# project2.net
KiCad netlist of a schematic drawn in EAGLE
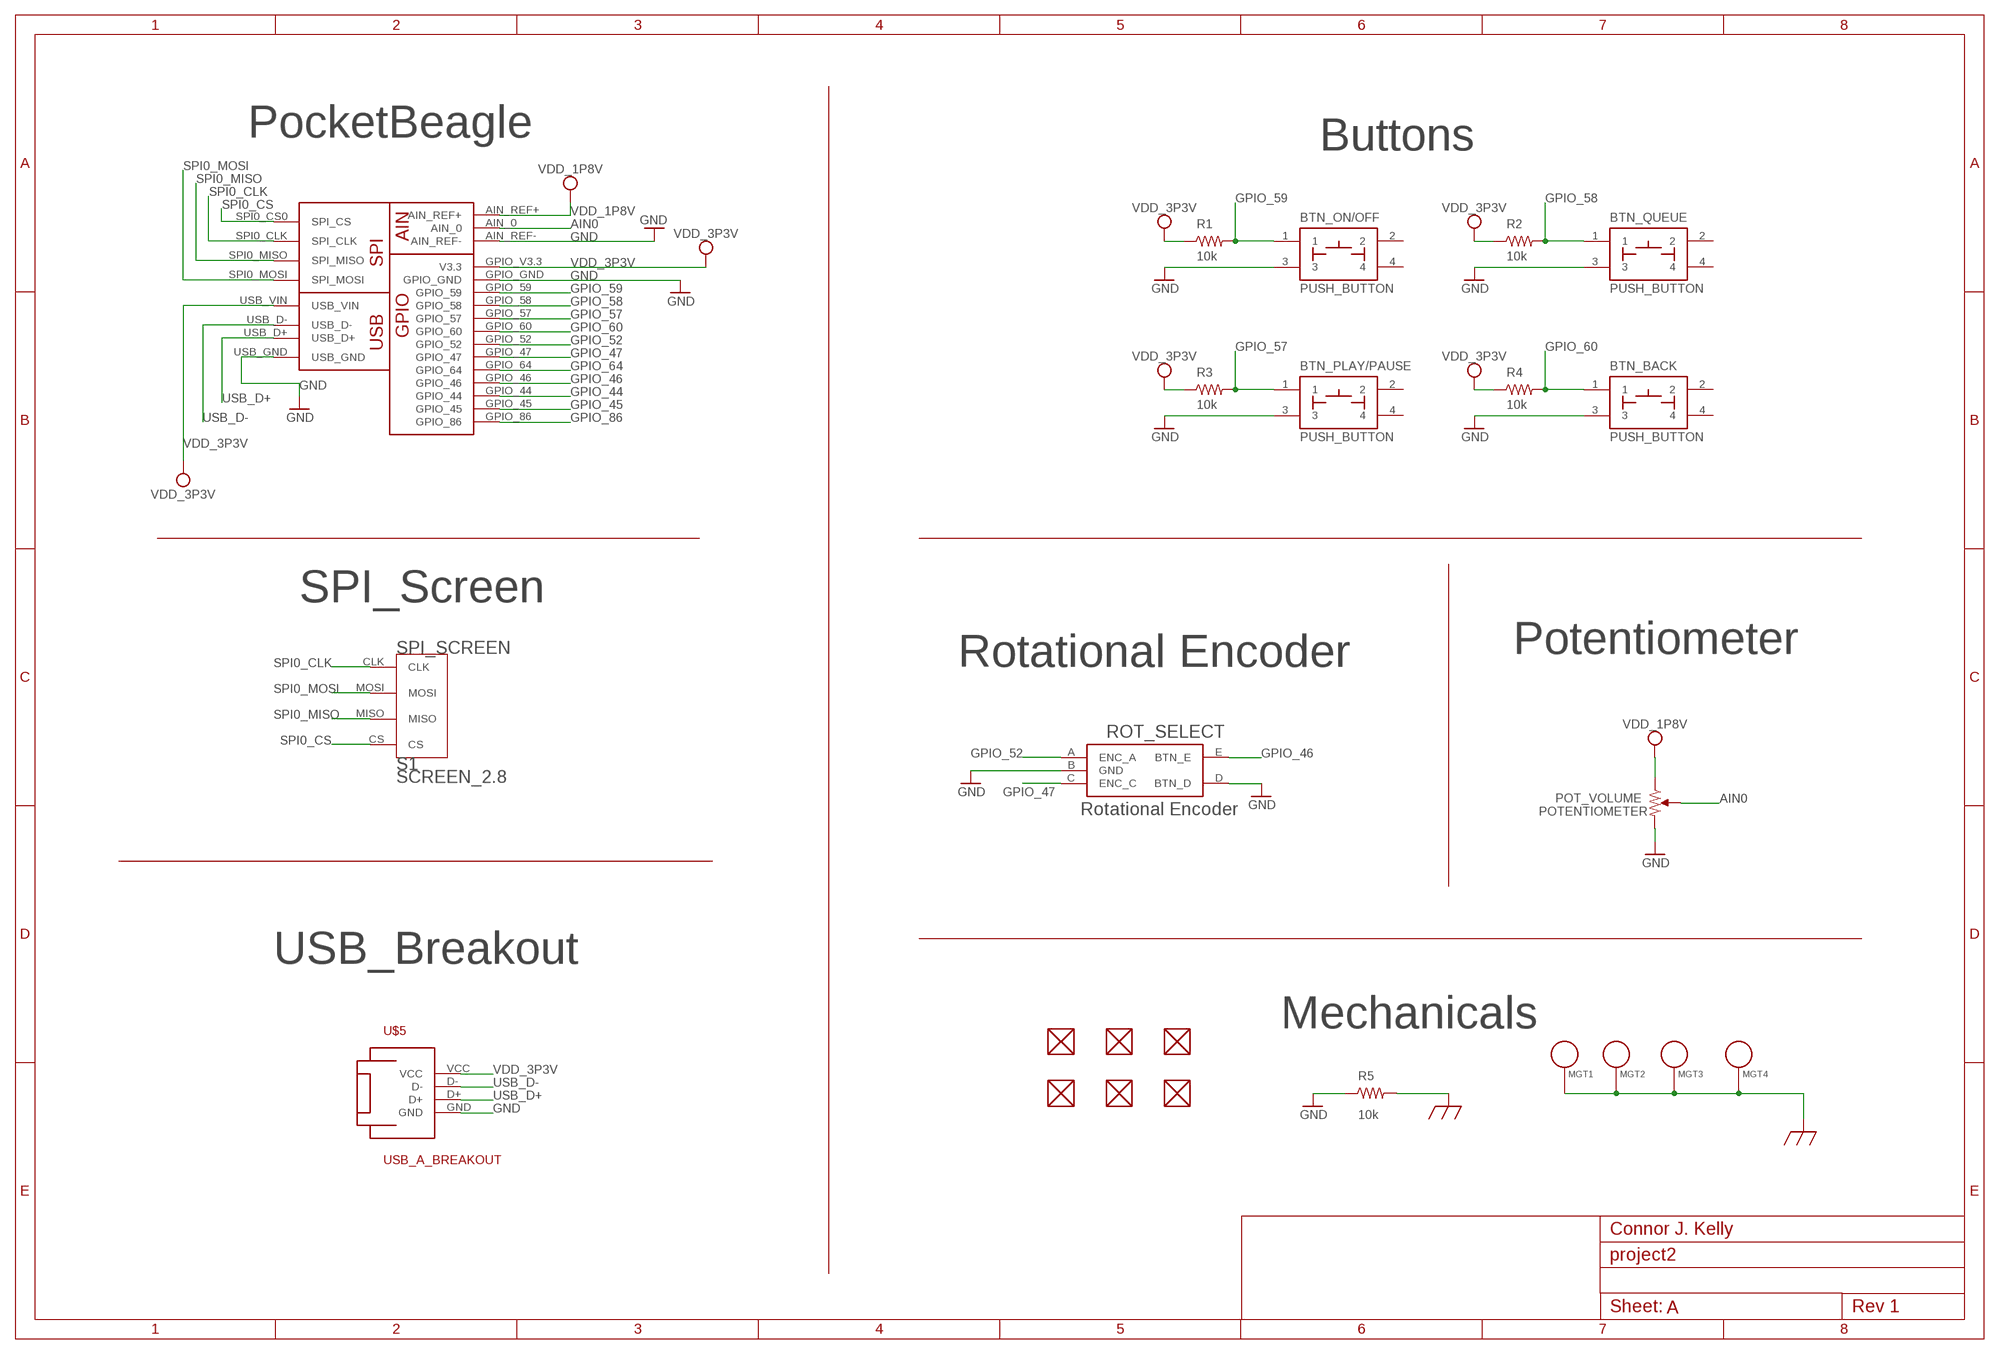
[diagram p0: schematic, sheet 1]

(export (version "E")
  (design (tool "Eeschema 10.0.6"))
  (components
    (comp (ref "BTN_BACK")
      (value "PUSH_BUTTON")
      (footprint "eagle-import:BUTTON_12.5MM")
      (fields (field (name "MF") "Adafruit"))
      (libsource (lib "eagle-import") (part "PUSH_BUTTON"))
    )
    (comp (ref "BTN_ON/OFF")
      (value "PUSH_BUTTON")
      (footprint "eagle-import:BUTTON_12.5MM")
      (fields (field (name "MF") "Adafruit"))
      (libsource (lib "eagle-import") (part "PUSH_BUTTON"))
    )
    (comp (ref "BTN_PLAY/PAUSE")
      (value "PUSH_BUTTON")
      (footprint "eagle-import:BUTTON_12.5MM")
      (fields (field (name "MF") "Adafruit"))
      (libsource (lib "eagle-import") (part "PUSH_BUTTON"))
    )
    (comp (ref "BTN_QUEUE")
      (value "PUSH_BUTTON")
      (footprint "eagle-import:BUTTON_12.5MM")
      (fields (field (name "MF") "Adafruit"))
      (libsource (lib "eagle-import") (part "PUSH_BUTTON"))
    )
    (comp (ref "FUD1")
      (value "FIDUCIAL")
      (footprint "eagle-import:FIDUCIAL_40MIL")
      (libsource (lib "eagle-import") (part "FIDUCIAL"))
    )
    (comp (ref "FUD2")
      (value "FIDUCIAL")
      (footprint "eagle-import:FIDUCIAL_40MIL")
      (libsource (lib "eagle-import") (part "FIDUCIAL"))
    )
    (comp (ref "FUD3")
      (value "FIDUCIAL")
      (footprint "eagle-import:FIDUCIAL_40MIL")
      (libsource (lib "eagle-import") (part "FIDUCIAL"))
    )
    (comp (ref "FUD4")
      (value "FIDUCIAL")
      (footprint "eagle-import:FIDUCIAL_40MIL")
      (libsource (lib "eagle-import") (part "FIDUCIAL"))
    )
    (comp (ref "FUD5")
      (value "FIDUCIAL")
      (footprint "eagle-import:FIDUCIAL_40MIL")
      (libsource (lib "eagle-import") (part "FIDUCIAL"))
    )
    (comp (ref "FUD6")
      (value "FIDUCIAL")
      (footprint "eagle-import:FIDUCIAL_40MIL")
      (libsource (lib "eagle-import") (part "FIDUCIAL"))
    )
    (comp (ref "MGT1")
      (value "MOUNTING_HOLE")
      (footprint "eagle-import:MOUNTING_HOLE")
      (libsource (lib "eagle-import") (part "MOUNTING_HOLE"))
    )
    (comp (ref "MGT2")
      (value "MOUNTING_HOLE")
      (footprint "eagle-import:MOUNTING_HOLE")
      (libsource (lib "eagle-import") (part "MOUNTING_HOLE"))
    )
    (comp (ref "MGT3")
      (value "MOUNTING_HOLE")
      (footprint "eagle-import:MOUNTING_HOLE")
      (libsource (lib "eagle-import") (part "MOUNTING_HOLE"))
    )
    (comp (ref "MGT4")
      (value "MOUNTING_HOLE")
      (footprint "eagle-import:MOUNTING_HOLE")
      (libsource (lib "eagle-import") (part "MOUNTING_HOLE"))
    )
    (comp (ref "POT_VOLUME")
      (value "POTENTIOMETER")
      (footprint "eagle-import:POT-PO90S")
      (fields (field (name "MF") "TT Electronics/BI"))
      (libsource (lib "eagle-import") (part "POTENTIOMETER"))
    )
    (comp (ref "R1")
      (value "10k")
      (footprint "eagle-import:R0402")
      (fields (field (name "MF") "Bournes Inc"))
      (libsource (lib "eagle-import") (part "R_R0402"))
    )
    (comp (ref "R2")
      (value "10k")
      (footprint "eagle-import:R0402")
      (fields (field (name "MF") "Bournes Inc"))
      (libsource (lib "eagle-import") (part "R_R0402"))
    )
    (comp (ref "R3")
      (value "10k")
      (footprint "eagle-import:R0402")
      (fields (field (name "MF") "Bournes Inc"))
      (libsource (lib "eagle-import") (part "R_R0402"))
    )
    (comp (ref "R4")
      (value "10k")
      (footprint "eagle-import:R0402")
      (fields (field (name "MF") "Bournes Inc"))
      (libsource (lib "eagle-import") (part "R_R0402"))
    )
    (comp (ref "R5")
      (value "10k")
      (footprint "eagle-import:R0402")
      (fields (field (name "MF") "Bournes Inc"))
      (libsource (lib "eagle-import") (part "R_R0402"))
    )
    (comp (ref "ROT_SELECT")
      (value "PEC16-4015F-S0024")
      (footprint "eagle-import:PEC16-4015F-S0024")
      (fields (field (name "MF") "Bourns"))
      (libsource (lib "eagle-import") (part "PEC16-4015F-S0024"))
    )
    (comp (ref "S1")
      (value "SCREEN_2.8")
      (footprint "eagle-import:SCREEN_2.8")
      (fields (field (name "MF") "Adafruit"))
      (libsource (lib "eagle-import") (part "SCREEN_2.8"))
    )
    (comp (ref "U$3")
      (value "POCKETBEAGLE")
      (footprint "eagle-import:POCKETBEAGLE")
      (fields (field (name "MF") "BeagleBoard"))
      (libsource (lib "eagle-import") (part "POCKETBEAGLE"))
    )
    (comp (ref "U$5")
      (value "USB_A_BREAKOUT")
      (footprint "eagle-import:USB_A_BREAKOUT")
      (fields (field (name "MF") "SparkFun"))
      (libsource (lib "eagle-import") (part "USB_A_BREAKOUT"))
    )
  )
  (nets
    (net (code "1") (name "/AIN0") (class "Default")
      (node (ref "POT_VOLUME") (pin "S") (pinfunction "S_S") (pintype "bidirectional"))
      (node (ref "U$3") (pin "AIN_0") (pinfunction "AIN_0_AIN_0") (pintype "bidirectional"))
    )
    (net (code "2") (name "/GPIO_44") (class "Default")
      (node (ref "U$3") (pin "GPIO_44") (pinfunction "GPIO_44_GPIO_44") (pintype "bidirectional"))
    )
    (net (code "3") (name "/GPIO_45") (class "Default")
      (node (ref "U$3") (pin "GPIO_45") (pinfunction "GPIO_45_GPIO_45") (pintype "bidirectional"))
    )
    (net (code "4") (name "/GPIO_46") (class "Default")
      (node (ref "ROT_SELECT") (pin "E") (pinfunction "BTN_E_E") (pintype "bidirectional"))
      (node (ref "U$3") (pin "GPIO_46") (pinfunction "GPIO_46_GPIO_46") (pintype "bidirectional"))
    )
    (net (code "5") (name "/GPIO_47") (class "Default")
      (node (ref "ROT_SELECT") (pin "C") (pinfunction "ENC_C_C") (pintype "bidirectional"))
      (node (ref "U$3") (pin "GPIO_47") (pinfunction "GPIO_47_GPIO_47") (pintype "bidirectional"))
    )
    (net (code "6") (name "/GPIO_52") (class "Default")
      (node (ref "ROT_SELECT") (pin "A") (pinfunction "ENC_A_A") (pintype "bidirectional"))
      (node (ref "U$3") (pin "GPIO_52") (pinfunction "GPIO_52_GPIO_52") (pintype "bidirectional"))
    )
    (net (code "7") (name "/GPIO_57") (class "Default")
      (node (ref "BTN_PLAY/PAUSE") (pin "1") (pinfunction "1_1") (pintype "bidirectional"))
      (node (ref "R3") (pin "2") (pinfunction "2_2") (pintype "passive"))
      (node (ref "U$3") (pin "GPIO_57") (pinfunction "GPIO_57_GPIO_57") (pintype "bidirectional"))
    )
    (net (code "8") (name "/GPIO_58") (class "Default")
      (node (ref "BTN_QUEUE") (pin "1") (pinfunction "1_1") (pintype "bidirectional"))
      (node (ref "R2") (pin "2") (pinfunction "2_2") (pintype "passive"))
      (node (ref "U$3") (pin "GPIO_58") (pinfunction "GPIO_58_GPIO_58") (pintype "bidirectional"))
    )
    (net (code "9") (name "/GPIO_59") (class "Default")
      (node (ref "BTN_ON/OFF") (pin "1") (pinfunction "1_1") (pintype "bidirectional"))
      (node (ref "R1") (pin "2") (pinfunction "2_2") (pintype "passive"))
      (node (ref "U$3") (pin "GPIO_59") (pinfunction "GPIO_59_GPIO_59") (pintype "bidirectional"))
    )
    (net (code "10") (name "/GPIO_60") (class "Default")
      (node (ref "BTN_BACK") (pin "1") (pinfunction "1_1") (pintype "bidirectional"))
      (node (ref "R4") (pin "2") (pinfunction "2_2") (pintype "passive"))
      (node (ref "U$3") (pin "GPIO_60") (pinfunction "GPIO_60_GPIO_60") (pintype "bidirectional"))
    )
    (net (code "11") (name "/GPIO_64") (class "Default")
      (node (ref "U$3") (pin "GPIO_64") (pinfunction "GPIO_64_GPIO_64") (pintype "bidirectional"))
    )
    (net (code "12") (name "/GPIO_86") (class "Default")
      (node (ref "U$3") (pin "GPIO_86") (pinfunction "GPIO_86_GPIO_86") (pintype "bidirectional"))
    )
    (net (code "13") (name "/SPI0_CLK") (class "Default")
      (node (ref "S1") (pin "CLK") (pinfunction "CLK_CLK") (pintype "bidirectional"))
      (node (ref "U$3") (pin "SPI0_CLK") (pinfunction "SPI_CLK_SPI0_CLK") (pintype "bidirectional"))
    )
    (net (code "14") (name "/SPI0_CS") (class "Default")
      (node (ref "S1") (pin "CS") (pinfunction "CS_CS") (pintype "bidirectional"))
      (node (ref "U$3") (pin "SPI0_CS0") (pinfunction "SPI_CS_SPI0_CS0") (pintype "bidirectional"))
    )
    (net (code "15") (name "/SPI0_MISO") (class "Default")
      (node (ref "S1") (pin "MISO") (pinfunction "MISO_MISO") (pintype "bidirectional"))
      (node (ref "U$3") (pin "SPI0_MISO") (pinfunction "SPI_MISO_SPI0_MISO") (pintype "bidirectional"))
    )
    (net (code "16") (name "/SPI0_MOSI") (class "Default")
      (node (ref "S1") (pin "MOSI") (pinfunction "MOSI_MOSI") (pintype "bidirectional"))
      (node (ref "U$3") (pin "SPI0_MOSI") (pinfunction "SPI_MOSI_SPI0_MOSI") (pintype "bidirectional"))
    )
    (net (code "17") (name "/USB_D+") (class "Default")
      (node (ref "U$3") (pin "USB_D+") (pinfunction "USB_D+_USB_D+") (pintype "bidirectional"))
      (node (ref "U$5") (pin "D+") (pinfunction "D+_D+") (pintype "bidirectional"))
    )
    (net (code "18") (name "/USB_D-") (class "Default")
      (node (ref "U$3") (pin "USB_D-") (pinfunction "USB_D-_USB_D-") (pintype "bidirectional"))
      (node (ref "U$5") (pin "D-") (pinfunction "D-_D-") (pintype "bidirectional"))
    )
    (net (code "19") (name "CGND") (class "Default")
      (node (ref "MGT1") (pin "P$1") (pinfunction "P$1_P$1") (pintype "bidirectional"))
      (node (ref "MGT2") (pin "P$1") (pinfunction "P$1_P$1") (pintype "bidirectional"))
      (node (ref "MGT3") (pin "P$1") (pinfunction "P$1_P$1") (pintype "bidirectional"))
      (node (ref "MGT4") (pin "P$1") (pinfunction "P$1_P$1") (pintype "bidirectional"))
      (node (ref "R5") (pin "2") (pinfunction "2_2") (pintype "passive"))
    )
    (net (code "20") (name "GND") (class "Default")
      (node (ref "BTN_BACK") (pin "3") (pinfunction "3_3") (pintype "bidirectional"))
      (node (ref "BTN_ON/OFF") (pin "3") (pinfunction "3_3") (pintype "bidirectional"))
      (node (ref "BTN_PLAY/PAUSE") (pin "3") (pinfunction "3_3") (pintype "bidirectional"))
      (node (ref "BTN_QUEUE") (pin "3") (pinfunction "3_3") (pintype "bidirectional"))
      (node (ref "POT_VOLUME") (pin "CW") (pinfunction "CW_CW") (pintype "passive"))
      (node (ref "R5") (pin "1") (pinfunction "1_1") (pintype "passive"))
      (node (ref "ROT_SELECT") (pin "B") (pinfunction "GND_B") (pintype "bidirectional"))
      (node (ref "ROT_SELECT") (pin "D") (pinfunction "BTN_D_D") (pintype "bidirectional"))
      (node (ref "U$3") (pin "AIN_REF-") (pinfunction "AIN_REF-_AIN_REF-") (pintype "bidirectional"))
      (node (ref "U$3") (pin "GPIO_GND") (pinfunction "GPIO_GND_GPIO_GND") (pintype "bidirectional"))
      (node (ref "U$3") (pin "USB_GND") (pinfunction "USB_GND_USB_GND") (pintype "bidirectional"))
      (node (ref "U$5") (pin "GND") (pinfunction "GND_GND") (pintype "bidirectional"))
    )
    (net (code "21") (name "VDD_1P8V") (class "Default")
      (node (ref "POT_VOLUME") (pin "CCW") (pinfunction "CCW_CCW") (pintype "passive"))
      (node (ref "U$3") (pin "AIN_REF+") (pinfunction "AIN_REF+_AIN_REF+") (pintype "bidirectional"))
    )
    (net (code "22") (name "VDD_3P3V") (class "Default")
      (node (ref "R1") (pin "1") (pinfunction "1_1") (pintype "passive"))
      (node (ref "R2") (pin "1") (pinfunction "1_1") (pintype "passive"))
      (node (ref "R3") (pin "1") (pinfunction "1_1") (pintype "passive"))
      (node (ref "R4") (pin "1") (pinfunction "1_1") (pintype "passive"))
      (node (ref "U$3") (pin "GPIO_V3.3") (pinfunction "V3.3_GPIO_V3.3") (pintype "bidirectional"))
      (node (ref "U$3") (pin "USB_VIN") (pinfunction "USB_VIN_USB_VIN") (pintype "bidirectional"))
      (node (ref "U$5") (pin "VCC") (pinfunction "VCC_VCC") (pintype "bidirectional"))
    )
    (net (code "23") (name "unconnected-(BTN_BACK-Pad2)") (class "Default")
      (node (ref "BTN_BACK") (pin "2") (pinfunction "2_2") (pintype "bidirectional"))
    )
    (net (code "24") (name "unconnected-(BTN_BACK-Pad4)") (class "Default")
      (node (ref "BTN_BACK") (pin "4") (pinfunction "4_4") (pintype "bidirectional"))
    )
    (net (code "25") (name "unconnected-(BTN_ON/OFF-Pad2)") (class "Default")
      (node (ref "BTN_ON/OFF") (pin "2") (pinfunction "2_2") (pintype "bidirectional"))
    )
    (net (code "26") (name "unconnected-(BTN_ON/OFF-Pad4)") (class "Default")
      (node (ref "BTN_ON/OFF") (pin "4") (pinfunction "4_4") (pintype "bidirectional"))
    )
    (net (code "27") (name "unconnected-(BTN_PLAY/PAUSE-Pad2)") (class "Default")
      (node (ref "BTN_PLAY/PAUSE") (pin "2") (pinfunction "2_2") (pintype "bidirectional"))
    )
    (net (code "28") (name "unconnected-(BTN_PLAY/PAUSE-Pad4)") (class "Default")
      (node (ref "BTN_PLAY/PAUSE") (pin "4") (pinfunction "4_4") (pintype "bidirectional"))
    )
    (net (code "29") (name "unconnected-(BTN_QUEUE-Pad2)") (class "Default")
      (node (ref "BTN_QUEUE") (pin "2") (pinfunction "2_2") (pintype "bidirectional"))
    )
    (net (code "30") (name "unconnected-(BTN_QUEUE-Pad4)") (class "Default")
      (node (ref "BTN_QUEUE") (pin "4") (pinfunction "4_4") (pintype "bidirectional"))
    )
    (net (code "31") (name "unconnected-(FUD1-PadP$1)") (class "Default")
      (node (ref "FUD1") (pin "P$1") (pinfunction "P$1_P$1") (pintype "no_connect"))
    )
    (net (code "32") (name "unconnected-(FUD2-PadP$1)") (class "Default")
      (node (ref "FUD2") (pin "P$1") (pinfunction "P$1_P$1") (pintype "no_connect"))
    )
    (net (code "33") (name "unconnected-(FUD3-PadP$1)") (class "Default")
      (node (ref "FUD3") (pin "P$1") (pinfunction "P$1_P$1") (pintype "no_connect"))
    )
    (net (code "34") (name "unconnected-(FUD4-PadP$1)") (class "Default")
      (node (ref "FUD4") (pin "P$1") (pinfunction "P$1_P$1") (pintype "no_connect"))
    )
    (net (code "35") (name "unconnected-(FUD5-PadP$1)") (class "Default")
      (node (ref "FUD5") (pin "P$1") (pinfunction "P$1_P$1") (pintype "no_connect"))
    )
    (net (code "36") (name "unconnected-(FUD6-PadP$1)") (class "Default")
      (node (ref "FUD6") (pin "P$1") (pinfunction "P$1_P$1") (pintype "no_connect"))
    )
  )
)
